# Sch_MEZON.net
KiCad netlist of a schematic drawn in Altium Designer
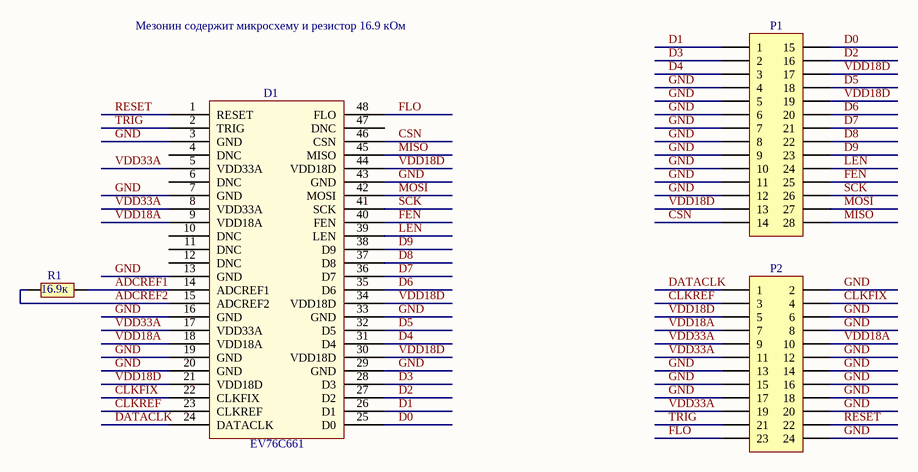
[diagram p0: Sch_MEZON.SchDoc]

(export (version "E")
  (design (tool "Eeschema 10.0.6"))
  (components
    (comp (ref "D1") (value "EV76C661") (footprint "EV76C661") (libsource (lib "Schlib") (part "EV76C661")))
    (comp (ref "P1")
      (value "Header 14X2A")
      (footprint "HDR2X14_CEN")
      (description "Header, 14-Pin, Dual row")
      (fields (field (name "PUBLISHER") "Altium Limited"))
      (libsource (lib "Miscellaneous Connectors") (part "Header 14X2A"))
    )
    (comp (ref "P2")
      (value "Header 12X2")
      (footprint "HDR2X12")
      (description "Header, 12-Pin, Dual row")
      (fields (field (name "PUBLISHER") "Altium Limited"))
      (libsource (lib "Miscellaneous Connectors") (part "Header 12X2"))
    )
    (comp (ref "R1") (value "16.9к") (footprint "RES") (libsource (lib "Schlib") (part "RES")))
  )
  (nets
    (net (code "1") (name "/ADCREF1") (class "Default")
      (node (ref "D1") (pin "14") (pinfunction "ADCREF1_14") (pintype "passive"))
      (node (ref "R1") (pin "2") (pinfunction "2_2") (pintype "passive"))
    )
    (net (code "2") (name "/ADCREF2") (class "Default")
      (node (ref "D1") (pin "15") (pinfunction "ADCREF2_15") (pintype "passive"))
      (node (ref "R1") (pin "1") (pinfunction "1_1") (pintype "passive"))
    )
    (net (code "3") (name "/CLKFIX") (class "Default")
      (node (ref "D1") (pin "22") (pinfunction "CLKFIX_22") (pintype "passive"))
      (node (ref "P2") (pin "4") (pinfunction "4_4") (pintype "passive"))
    )
    (net (code "4") (name "/CLKREF") (class "Default")
      (node (ref "D1") (pin "23") (pinfunction "CLKREF_23") (pintype "passive"))
      (node (ref "P2") (pin "3") (pinfunction "3_3") (pintype "passive"))
    )
    (net (code "5") (name "/CSN") (class "Default")
      (node (ref "D1") (pin "46") (pinfunction "CSN_46") (pintype "passive"))
      (node (ref "P1") (pin "14") (pinfunction "14_14") (pintype "passive"))
    )
    (net (code "6") (name "/D0") (class "Default")
      (node (ref "D1") (pin "25") (pinfunction "D0_25") (pintype "passive"))
      (node (ref "P1") (pin "15") (pinfunction "15_15") (pintype "passive"))
    )
    (net (code "7") (name "/D1") (class "Default")
      (node (ref "D1") (pin "26") (pinfunction "D1_26") (pintype "passive"))
      (node (ref "P1") (pin "1") (pinfunction "1_1") (pintype "passive"))
    )
    (net (code "8") (name "/D2") (class "Default")
      (node (ref "D1") (pin "27") (pinfunction "D2_27") (pintype "passive"))
      (node (ref "P1") (pin "16") (pinfunction "16_16") (pintype "passive"))
    )
    (net (code "9") (name "/D3") (class "Default")
      (node (ref "D1") (pin "28") (pinfunction "D3_28") (pintype "passive"))
      (node (ref "P1") (pin "2") (pinfunction "2_2") (pintype "passive"))
    )
    (net (code "10") (name "/D4") (class "Default")
      (node (ref "D1") (pin "31") (pinfunction "D4_31") (pintype "passive"))
      (node (ref "P1") (pin "3") (pinfunction "3_3") (pintype "passive"))
    )
    (net (code "11") (name "/D5") (class "Default")
      (node (ref "D1") (pin "32") (pinfunction "D5_32") (pintype "passive"))
      (node (ref "P1") (pin "18") (pinfunction "18_18") (pintype "passive"))
    )
    (net (code "12") (name "/D6") (class "Default")
      (node (ref "D1") (pin "35") (pinfunction "D6_35") (pintype "passive"))
      (node (ref "P1") (pin "20") (pinfunction "20_20") (pintype "passive"))
    )
    (net (code "13") (name "/D7") (class "Default")
      (node (ref "D1") (pin "36") (pinfunction "D7_36") (pintype "passive"))
      (node (ref "P1") (pin "21") (pinfunction "21_21") (pintype "passive"))
    )
    (net (code "14") (name "/D8") (class "Default")
      (node (ref "D1") (pin "37") (pinfunction "D8_37") (pintype "passive"))
      (node (ref "P1") (pin "22") (pinfunction "22_22") (pintype "passive"))
    )
    (net (code "15") (name "/D9") (class "Default")
      (node (ref "D1") (pin "38") (pinfunction "D9_38") (pintype "passive"))
      (node (ref "P1") (pin "23") (pinfunction "23_23") (pintype "passive"))
    )
    (net (code "16") (name "/DATACLK") (class "Default")
      (node (ref "D1") (pin "24") (pinfunction "DATACLK_24") (pintype "passive"))
      (node (ref "P2") (pin "1") (pinfunction "1_1") (pintype "passive"))
    )
    (net (code "17") (name "/FEN") (class "Default")
      (node (ref "D1") (pin "40") (pinfunction "FEN_40") (pintype "passive"))
      (node (ref "P1") (pin "25") (pinfunction "25_25") (pintype "passive"))
    )
    (net (code "18") (name "/FLO") (class "Default")
      (node (ref "D1") (pin "48") (pinfunction "FLO_48") (pintype "passive"))
      (node (ref "P2") (pin "23") (pinfunction "23_23") (pintype "passive"))
    )
    (net (code "19") (name "/GND") (class "Default")
      (node (ref "D1") (pin "13") (pinfunction "GND_13") (pintype "passive"))
      (node (ref "D1") (pin "16") (pinfunction "GND_16") (pintype "passive"))
      (node (ref "D1") (pin "19") (pinfunction "GND_19") (pintype "passive"))
      (node (ref "D1") (pin "20") (pinfunction "GND_20") (pintype "passive"))
      (node (ref "D1") (pin "29") (pinfunction "GND_29") (pintype "passive"))
      (node (ref "D1") (pin "3") (pinfunction "GND_3") (pintype "passive"))
      (node (ref "D1") (pin "33") (pinfunction "GND_33") (pintype "passive"))
      (node (ref "D1") (pin "43") (pinfunction "GND_43") (pintype "passive"))
      (node (ref "D1") (pin "7") (pinfunction "GND_7") (pintype "passive"))
      (node (ref "P1") (pin "10") (pinfunction "10_10") (pintype "passive"))
      (node (ref "P1") (pin "11") (pinfunction "11_11") (pintype "passive"))
      (node (ref "P1") (pin "12") (pinfunction "12_12") (pintype "passive"))
      (node (ref "P1") (pin "4") (pinfunction "4_4") (pintype "passive"))
      (node (ref "P1") (pin "5") (pinfunction "5_5") (pintype "passive"))
      (node (ref "P1") (pin "6") (pinfunction "6_6") (pintype "passive"))
      (node (ref "P1") (pin "7") (pinfunction "7_7") (pintype "passive"))
      (node (ref "P1") (pin "8") (pinfunction "8_8") (pintype "passive"))
      (node (ref "P1") (pin "9") (pinfunction "9_9") (pintype "passive"))
      (node (ref "P2") (pin "12") (pinfunction "12_12") (pintype "passive"))
      (node (ref "P2") (pin "13") (pinfunction "13_13") (pintype "passive"))
      (node (ref "P2") (pin "14") (pinfunction "14_14") (pintype "passive"))
      (node (ref "P2") (pin "15") (pinfunction "15_15") (pintype "passive"))
      (node (ref "P2") (pin "16") (pinfunction "16_16") (pintype "passive"))
      (node (ref "P2") (pin "17") (pinfunction "17_17") (pintype "passive"))
      (node (ref "P2") (pin "18") (pinfunction "18_18") (pintype "passive"))
      (node (ref "P2") (pin "2") (pinfunction "2_2") (pintype "passive"))
      (node (ref "P2") (pin "20") (pinfunction "20_20") (pintype "passive"))
      (node (ref "P2") (pin "24") (pinfunction "24_24") (pintype "passive"))
      (node (ref "P2") (pin "6") (pinfunction "6_6") (pintype "passive"))
      (node (ref "P2") (pin "8") (pinfunction "8_8") (pintype "passive"))
    )
    (net (code "20") (name "/LEN") (class "Default")
      (node (ref "D1") (pin "39") (pinfunction "LEN_39") (pintype "passive"))
      (node (ref "P1") (pin "24") (pinfunction "24_24") (pintype "passive"))
    )
    (net (code "21") (name "/MISO") (class "Default")
      (node (ref "D1") (pin "45") (pinfunction "MISO_45") (pintype "passive"))
      (node (ref "P1") (pin "28") (pinfunction "28_28") (pintype "passive"))
    )
    (net (code "22") (name "/MOSI") (class "Default")
      (node (ref "D1") (pin "42") (pinfunction "MOSI_42") (pintype "passive"))
      (node (ref "P1") (pin "27") (pinfunction "27_27") (pintype "passive"))
    )
    (net (code "23") (name "/RESET") (class "Default")
      (node (ref "D1") (pin "1") (pinfunction "RESET_1") (pintype "passive"))
      (node (ref "P2") (pin "22") (pinfunction "22_22") (pintype "passive"))
    )
    (net (code "24") (name "/SCK") (class "Default")
      (node (ref "D1") (pin "41") (pinfunction "SCK_41") (pintype "passive"))
      (node (ref "P1") (pin "26") (pinfunction "26_26") (pintype "passive"))
    )
    (net (code "25") (name "/TRIG") (class "Default")
      (node (ref "D1") (pin "2") (pinfunction "TRIG_2") (pintype "passive"))
      (node (ref "P2") (pin "21") (pinfunction "21_21") (pintype "passive"))
    )
    (net (code "26") (name "/VDD18A") (class "Default")
      (node (ref "D1") (pin "18") (pinfunction "VDD18A_18") (pintype "passive"))
      (node (ref "D1") (pin "9") (pinfunction "VDD18A_9") (pintype "passive"))
      (node (ref "P2") (pin "10") (pinfunction "10_10") (pintype "passive"))
      (node (ref "P2") (pin "7") (pinfunction "7_7") (pintype "passive"))
    )
    (net (code "27") (name "/VDD18D") (class "Default")
      (node (ref "D1") (pin "21") (pinfunction "VDD18D_21") (pintype "passive"))
      (node (ref "D1") (pin "30") (pinfunction "VDD18D_30") (pintype "passive"))
      (node (ref "D1") (pin "34") (pinfunction "VDD18D_34") (pintype "passive"))
      (node (ref "D1") (pin "44") (pinfunction "VDD18D_44") (pintype "passive"))
      (node (ref "P1") (pin "13") (pinfunction "13_13") (pintype "passive"))
      (node (ref "P1") (pin "17") (pinfunction "17_17") (pintype "passive"))
      (node (ref "P1") (pin "19") (pinfunction "19_19") (pintype "passive"))
      (node (ref "P2") (pin "5") (pinfunction "5_5") (pintype "passive"))
    )
    (net (code "28") (name "/VDD33A") (class "Default")
      (node (ref "D1") (pin "17") (pinfunction "VDD33A_17") (pintype "passive"))
      (node (ref "D1") (pin "5") (pinfunction "VDD33A_5") (pintype "passive"))
      (node (ref "D1") (pin "8") (pinfunction "VDD33A_8") (pintype "passive"))
      (node (ref "P2") (pin "11") (pinfunction "11_11") (pintype "passive"))
      (node (ref "P2") (pin "19") (pinfunction "19_19") (pintype "passive"))
      (node (ref "P2") (pin "9") (pinfunction "9_9") (pintype "passive"))
    )
    (net (code "29") (name "unconnected-(D1-DNC-Pad4)") (class "Default")
      (node (ref "D1") (pin "4") (pinfunction "DNC_4") (pintype "passive"))
    )
    (net (code "30") (name "unconnected-(D1-DNC-Pad6)") (class "Default")
      (node (ref "D1") (pin "6") (pinfunction "DNC_6") (pintype "passive"))
    )
    (net (code "31") (name "unconnected-(D1-DNC-Pad10)") (class "Default")
      (node (ref "D1") (pin "10") (pinfunction "DNC_10") (pintype "passive"))
    )
    (net (code "32") (name "unconnected-(D1-DNC-Pad11)") (class "Default")
      (node (ref "D1") (pin "11") (pinfunction "DNC_11") (pintype "passive"))
    )
    (net (code "33") (name "unconnected-(D1-DNC-Pad12)") (class "Default")
      (node (ref "D1") (pin "12") (pinfunction "DNC_12") (pintype "passive"))
    )
    (net (code "34") (name "unconnected-(D1-DNC-Pad47)") (class "Default")
      (node (ref "D1") (pin "47") (pinfunction "DNC_47") (pintype "passive"))
    )
  )
)
